# barometr.net
KiCad netlist of a schematic drawn in EAGLE
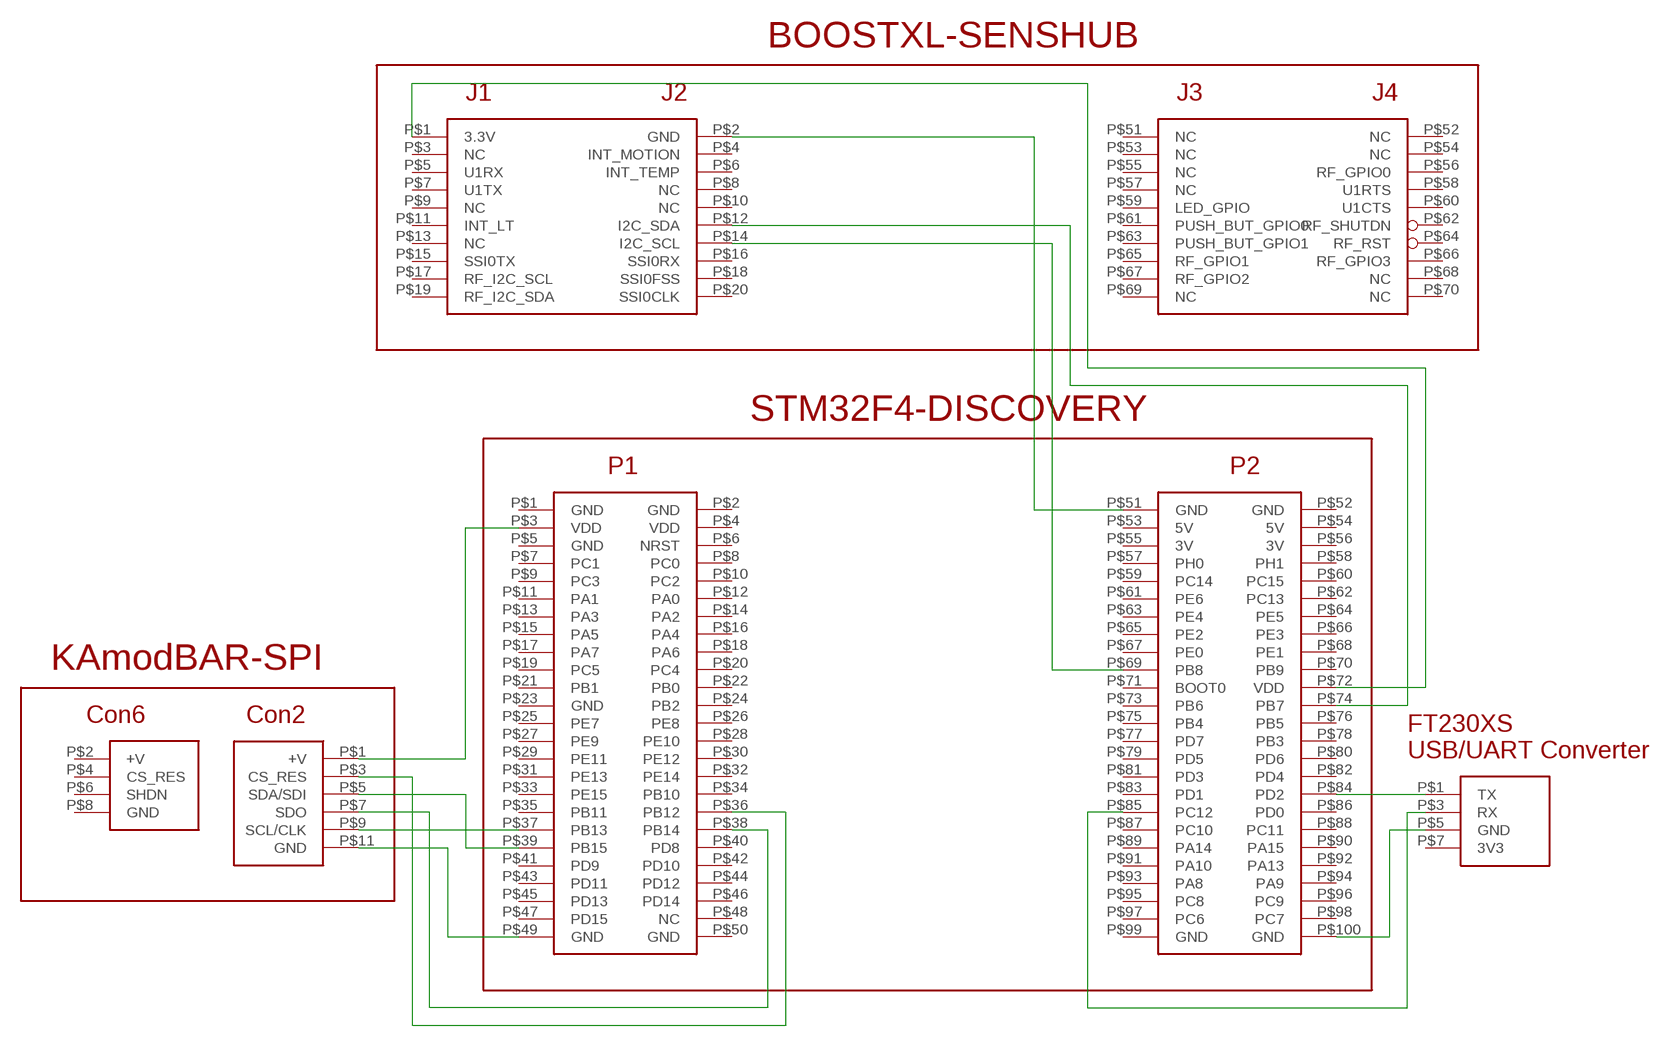
[diagram p0: schematic, sheet 1]

(export (version "E")
  (design (tool "Eeschema 10.0.6"))
  (components
    (comp (ref "U$1")
      (value "STM32F4-DISCOVERY")
      (footprint "eagle-import:STM32F4-DISCOVERY")
      (libsource (lib "eagle-import") (part "STM32F4-DISCOVERY"))
    )
    (comp (ref "U$2")
      (value "BOOSTXL-SENSHUB")
      (footprint "eagle-import:BOOSTXL-SENSHUB")
      (libsource (lib "eagle-import") (part "BOOSTXL-SENSHUB"))
    )
    (comp (ref "U$3")
      (value "KAMODBAR-SPI")
      (footprint "eagle-import:KAMODBAR-SPI")
      (libsource (lib "eagle-import") (part "KAMODBAR-SPI"))
    )
    (comp (ref "U$4")
      (value "FT230XS_UART_USB_CONVERTER")
      (footprint "eagle-import:FT230XS_UART_USB_CONVERTER")
      (libsource (lib "eagle-import") (part "FT230XS_UART_USB_CONVERTER"))
    )
  )
  (nets
    (net (code "1") (name "Net-(U$1-GND-PadP$49)") (class "Default")
      (node (ref "U$1") (pin "P$49") (pinfunction "GND_P$49") (pintype "bidirectional"))
      (node (ref "U$3") (pin "P$11") (pinfunction "GND_P$11") (pintype "bidirectional"))
    )
    (net (code "2") (name "Net-(U$1-PB7)") (class "Default")
      (node (ref "U$1") (pin "P$74") (pinfunction "PB7_P$74") (pintype "bidirectional"))
      (node (ref "U$2") (pin "P$12") (pinfunction "I2C_SDA_P$12") (pintype "bidirectional"))
    )
    (net (code "3") (name "Net-(U$1-PB8)") (class "Default")
      (node (ref "U$1") (pin "P$69") (pinfunction "PB8_P$69") (pintype "bidirectional"))
      (node (ref "U$2") (pin "P$14") (pinfunction "I2C_SCL_P$14") (pintype "bidirectional"))
    )
    (net (code "4") (name "Net-(U$1-PB12)") (class "Default")
      (node (ref "U$1") (pin "P$36") (pinfunction "PB12_P$36") (pintype "bidirectional"))
      (node (ref "U$3") (pin "P$3") (pinfunction "CS_RES_P$3") (pintype "bidirectional"))
    )
    (net (code "5") (name "Net-(U$1-PB13)") (class "Default")
      (node (ref "U$1") (pin "P$37") (pinfunction "PB13_P$37") (pintype "bidirectional"))
      (node (ref "U$3") (pin "P$9") (pinfunction "SCL/CLK_P$9") (pintype "bidirectional"))
    )
    (net (code "6") (name "Net-(U$1-PB14)") (class "Default")
      (node (ref "U$1") (pin "P$38") (pinfunction "PB14_P$38") (pintype "bidirectional"))
      (node (ref "U$3") (pin "P$7") (pinfunction "SDO_P$7") (pintype "bidirectional"))
    )
    (net (code "7") (name "Net-(U$1-PB15)") (class "Default")
      (node (ref "U$1") (pin "P$39") (pinfunction "PB15_P$39") (pintype "bidirectional"))
      (node (ref "U$3") (pin "P$5") (pinfunction "SDA/SDI_P$5") (pintype "bidirectional"))
    )
    (net (code "8") (name "Net-(U$1-PC12)") (class "Default")
      (node (ref "U$1") (pin "P$85") (pinfunction "PC12_P$85") (pintype "bidirectional"))
      (node (ref "U$4") (pin "P$3") (pinfunction "RX_P$3") (pintype "bidirectional"))
    )
    (net (code "9") (name "Net-(U$1-PD2)") (class "Default")
      (node (ref "U$1") (pin "P$84") (pinfunction "PD2_P$84") (pintype "bidirectional"))
      (node (ref "U$4") (pin "P$1") (pinfunction "TX_P$1") (pintype "bidirectional"))
    )
    (net (code "10") (name "Net-(U$1-VDD-PadP$3)") (class "Default")
      (node (ref "U$1") (pin "P$3") (pinfunction "VDD_P$3") (pintype "bidirectional"))
      (node (ref "U$3") (pin "P$1") (pinfunction "+V_P$1") (pintype "bidirectional"))
    )
    (net (code "11") (name "Net-(U$2-3.3V)") (class "Default")
      (node (ref "U$1") (pin "P$72") (pinfunction "VDD_P$72") (pintype "bidirectional"))
      (node (ref "U$2") (pin "P$1") (pinfunction "3.3V_P$1") (pintype "bidirectional"))
    )
    (net (code "12") (name "Net-(U$2-GND)") (class "Default")
      (node (ref "U$1") (pin "P$51") (pinfunction "GND_P$51") (pintype "bidirectional"))
      (node (ref "U$2") (pin "P$2") (pinfunction "GND_P$2") (pintype "bidirectional"))
    )
    (net (code "13") (name "Net-(U$4-GND)") (class "Default")
      (node (ref "U$1") (pin "P$100") (pinfunction "GND_P$100") (pintype "bidirectional"))
      (node (ref "U$4") (pin "P$5") (pinfunction "GND_P$5") (pintype "bidirectional"))
    )
    (net (code "14") (name "unconnected-(U$1-3V-PadP$55)") (class "Default")
      (node (ref "U$1") (pin "P$55") (pinfunction "3V_P$55") (pintype "bidirectional"))
    )
    (net (code "15") (name "unconnected-(U$1-3V-PadP$56)") (class "Default")
      (node (ref "U$1") (pin "P$56") (pinfunction "3V_P$56") (pintype "bidirectional"))
    )
    (net (code "16") (name "unconnected-(U$1-5V-PadP$53)") (class "Default")
      (node (ref "U$1") (pin "P$53") (pinfunction "5V_P$53") (pintype "bidirectional"))
    )
    (net (code "17") (name "unconnected-(U$1-5V-PadP$54)") (class "Default")
      (node (ref "U$1") (pin "P$54") (pinfunction "5V_P$54") (pintype "bidirectional"))
    )
    (net (code "18") (name "unconnected-(U$1-BOOT0-PadP$71)") (class "Default")
      (node (ref "U$1") (pin "P$71") (pinfunction "BOOT0_P$71") (pintype "bidirectional"))
    )
    (net (code "19") (name "unconnected-(U$1-GND-PadP$1)") (class "Default")
      (node (ref "U$1") (pin "P$1") (pinfunction "GND_P$1") (pintype "bidirectional"))
    )
    (net (code "20") (name "unconnected-(U$1-GND-PadP$2)") (class "Default")
      (node (ref "U$1") (pin "P$2") (pinfunction "GND_P$2") (pintype "bidirectional"))
    )
    (net (code "21") (name "unconnected-(U$1-GND-PadP$5)") (class "Default")
      (node (ref "U$1") (pin "P$5") (pinfunction "GND_P$5") (pintype "bidirectional"))
    )
    (net (code "22") (name "unconnected-(U$1-GND-PadP$23)") (class "Default")
      (node (ref "U$1") (pin "P$23") (pinfunction "GND_P$23") (pintype "bidirectional"))
    )
    (net (code "23") (name "unconnected-(U$1-GND-PadP$50)") (class "Default")
      (node (ref "U$1") (pin "P$50") (pinfunction "GND_P$50") (pintype "bidirectional"))
    )
    (net (code "24") (name "unconnected-(U$1-GND-PadP$52)") (class "Default")
      (node (ref "U$1") (pin "P$52") (pinfunction "GND_P$52") (pintype "bidirectional"))
    )
    (net (code "25") (name "unconnected-(U$1-GND-PadP$99)") (class "Default")
      (node (ref "U$1") (pin "P$99") (pinfunction "GND_P$99") (pintype "bidirectional"))
    )
    (net (code "26") (name "unconnected-(U$1-NC-PadP$48)") (class "Default")
      (node (ref "U$1") (pin "P$48") (pinfunction "NC_P$48") (pintype "bidirectional"))
    )
    (net (code "27") (name "unconnected-(U$1-NRST-PadP$6)") (class "Default")
      (node (ref "U$1") (pin "P$6") (pinfunction "NRST_P$6") (pintype "bidirectional"))
    )
    (net (code "28") (name "unconnected-(U$1-PA0-PadP$12)") (class "Default")
      (node (ref "U$1") (pin "P$12") (pinfunction "PA0_P$12") (pintype "bidirectional"))
    )
    (net (code "29") (name "unconnected-(U$1-PA1-PadP$11)") (class "Default")
      (node (ref "U$1") (pin "P$11") (pinfunction "PA1_P$11") (pintype "bidirectional"))
    )
    (net (code "30") (name "unconnected-(U$1-PA2-PadP$14)") (class "Default")
      (node (ref "U$1") (pin "P$14") (pinfunction "PA2_P$14") (pintype "bidirectional"))
    )
    (net (code "31") (name "unconnected-(U$1-PA3-PadP$13)") (class "Default")
      (node (ref "U$1") (pin "P$13") (pinfunction "PA3_P$13") (pintype "bidirectional"))
    )
    (net (code "32") (name "unconnected-(U$1-PA4-PadP$16)") (class "Default")
      (node (ref "U$1") (pin "P$16") (pinfunction "PA4_P$16") (pintype "bidirectional"))
    )
    (net (code "33") (name "unconnected-(U$1-PA5-PadP$15)") (class "Default")
      (node (ref "U$1") (pin "P$15") (pinfunction "PA5_P$15") (pintype "bidirectional"))
    )
    (net (code "34") (name "unconnected-(U$1-PA6-PadP$18)") (class "Default")
      (node (ref "U$1") (pin "P$18") (pinfunction "PA6_P$18") (pintype "bidirectional"))
    )
    (net (code "35") (name "unconnected-(U$1-PA7-PadP$17)") (class "Default")
      (node (ref "U$1") (pin "P$17") (pinfunction "PA7_P$17") (pintype "bidirectional"))
    )
    (net (code "36") (name "unconnected-(U$1-PA8-PadP$93)") (class "Default")
      (node (ref "U$1") (pin "P$93") (pinfunction "PA8_P$93") (pintype "bidirectional"))
    )
    (net (code "37") (name "unconnected-(U$1-PA9-PadP$94)") (class "Default")
      (node (ref "U$1") (pin "P$94") (pinfunction "PA9_P$94") (pintype "bidirectional"))
    )
    (net (code "38") (name "unconnected-(U$1-PA10-PadP$91)") (class "Default")
      (node (ref "U$1") (pin "P$91") (pinfunction "PA10_P$91") (pintype "bidirectional"))
    )
    (net (code "39") (name "unconnected-(U$1-PA13-PadP$92)") (class "Default")
      (node (ref "U$1") (pin "P$92") (pinfunction "PA13_P$92") (pintype "bidirectional"))
    )
    (net (code "40") (name "unconnected-(U$1-PA14-PadP$89)") (class "Default")
      (node (ref "U$1") (pin "P$89") (pinfunction "PA14_P$89") (pintype "bidirectional"))
    )
    (net (code "41") (name "unconnected-(U$1-PA15-PadP$90)") (class "Default")
      (node (ref "U$1") (pin "P$90") (pinfunction "PA15_P$90") (pintype "bidirectional"))
    )
    (net (code "42") (name "unconnected-(U$1-PB0-PadP$22)") (class "Default")
      (node (ref "U$1") (pin "P$22") (pinfunction "PB0_P$22") (pintype "bidirectional"))
    )
    (net (code "43") (name "unconnected-(U$1-PB1-PadP$21)") (class "Default")
      (node (ref "U$1") (pin "P$21") (pinfunction "PB1_P$21") (pintype "bidirectional"))
    )
    (net (code "44") (name "unconnected-(U$1-PB2-PadP$24)") (class "Default")
      (node (ref "U$1") (pin "P$24") (pinfunction "PB2_P$24") (pintype "bidirectional"))
    )
    (net (code "45") (name "unconnected-(U$1-PB3-PadP$78)") (class "Default")
      (node (ref "U$1") (pin "P$78") (pinfunction "PB3_P$78") (pintype "bidirectional"))
    )
    (net (code "46") (name "unconnected-(U$1-PB4-PadP$75)") (class "Default")
      (node (ref "U$1") (pin "P$75") (pinfunction "PB4_P$75") (pintype "bidirectional"))
    )
    (net (code "47") (name "unconnected-(U$1-PB5-PadP$76)") (class "Default")
      (node (ref "U$1") (pin "P$76") (pinfunction "PB5_P$76") (pintype "bidirectional"))
    )
    (net (code "48") (name "unconnected-(U$1-PB6-PadP$73)") (class "Default")
      (node (ref "U$1") (pin "P$73") (pinfunction "PB6_P$73") (pintype "bidirectional"))
    )
    (net (code "49") (name "unconnected-(U$1-PB9-PadP$70)") (class "Default")
      (node (ref "U$1") (pin "P$70") (pinfunction "PB9_P$70") (pintype "bidirectional"))
    )
    (net (code "50") (name "unconnected-(U$1-PB10-PadP$34)") (class "Default")
      (node (ref "U$1") (pin "P$34") (pinfunction "PB10_P$34") (pintype "bidirectional"))
    )
    (net (code "51") (name "unconnected-(U$1-PB11-PadP$35)") (class "Default")
      (node (ref "U$1") (pin "P$35") (pinfunction "PB11_P$35") (pintype "bidirectional"))
    )
    (net (code "52") (name "unconnected-(U$1-PC0-PadP$8)") (class "Default")
      (node (ref "U$1") (pin "P$8") (pinfunction "PC0_P$8") (pintype "bidirectional"))
    )
    (net (code "53") (name "unconnected-(U$1-PC1-PadP$7)") (class "Default")
      (node (ref "U$1") (pin "P$7") (pinfunction "PC1_P$7") (pintype "bidirectional"))
    )
    (net (code "54") (name "unconnected-(U$1-PC2-PadP$10)") (class "Default")
      (node (ref "U$1") (pin "P$10") (pinfunction "PC2_P$10") (pintype "bidirectional"))
    )
    (net (code "55") (name "unconnected-(U$1-PC3-PadP$9)") (class "Default")
      (node (ref "U$1") (pin "P$9") (pinfunction "PC3_P$9") (pintype "bidirectional"))
    )
    (net (code "56") (name "unconnected-(U$1-PC4-PadP$20)") (class "Default")
      (node (ref "U$1") (pin "P$20") (pinfunction "PC4_P$20") (pintype "bidirectional"))
    )
    (net (code "57") (name "unconnected-(U$1-PC5-PadP$19)") (class "Default")
      (node (ref "U$1") (pin "P$19") (pinfunction "PC5_P$19") (pintype "bidirectional"))
    )
    (net (code "58") (name "unconnected-(U$1-PC6-PadP$97)") (class "Default")
      (node (ref "U$1") (pin "P$97") (pinfunction "PC6_P$97") (pintype "bidirectional"))
    )
    (net (code "59") (name "unconnected-(U$1-PC7-PadP$98)") (class "Default")
      (node (ref "U$1") (pin "P$98") (pinfunction "PC7_P$98") (pintype "bidirectional"))
    )
    (net (code "60") (name "unconnected-(U$1-PC8-PadP$95)") (class "Default")
      (node (ref "U$1") (pin "P$95") (pinfunction "PC8_P$95") (pintype "bidirectional"))
    )
    (net (code "61") (name "unconnected-(U$1-PC9-PadP$96)") (class "Default")
      (node (ref "U$1") (pin "P$96") (pinfunction "PC9_P$96") (pintype "bidirectional"))
    )
    (net (code "62") (name "unconnected-(U$1-PC10-PadP$87)") (class "Default")
      (node (ref "U$1") (pin "P$87") (pinfunction "PC10_P$87") (pintype "bidirectional"))
    )
    (net (code "63") (name "unconnected-(U$1-PC11-PadP$88)") (class "Default")
      (node (ref "U$1") (pin "P$88") (pinfunction "PC11_P$88") (pintype "bidirectional"))
    )
    (net (code "64") (name "unconnected-(U$1-PC13-PadP$62)") (class "Default")
      (node (ref "U$1") (pin "P$62") (pinfunction "PC13_P$62") (pintype "bidirectional"))
    )
    (net (code "65") (name "unconnected-(U$1-PC14-PadP$59)") (class "Default")
      (node (ref "U$1") (pin "P$59") (pinfunction "PC14_P$59") (pintype "bidirectional"))
    )
    (net (code "66") (name "unconnected-(U$1-PC15-PadP$60)") (class "Default")
      (node (ref "U$1") (pin "P$60") (pinfunction "PC15_P$60") (pintype "bidirectional"))
    )
    (net (code "67") (name "unconnected-(U$1-PD0-PadP$86)") (class "Default")
      (node (ref "U$1") (pin "P$86") (pinfunction "PD0_P$86") (pintype "bidirectional"))
    )
    (net (code "68") (name "unconnected-(U$1-PD1-PadP$83)") (class "Default")
      (node (ref "U$1") (pin "P$83") (pinfunction "PD1_P$83") (pintype "bidirectional"))
    )
    (net (code "69") (name "unconnected-(U$1-PD3-PadP$81)") (class "Default")
      (node (ref "U$1") (pin "P$81") (pinfunction "PD3_P$81") (pintype "bidirectional"))
    )
    (net (code "70") (name "unconnected-(U$1-PD4-PadP$82)") (class "Default")
      (node (ref "U$1") (pin "P$82") (pinfunction "PD4_P$82") (pintype "bidirectional"))
    )
    (net (code "71") (name "unconnected-(U$1-PD5-PadP$79)") (class "Default")
      (node (ref "U$1") (pin "P$79") (pinfunction "PD5_P$79") (pintype "bidirectional"))
    )
    (net (code "72") (name "unconnected-(U$1-PD6-PadP$80)") (class "Default")
      (node (ref "U$1") (pin "P$80") (pinfunction "PD6_P$80") (pintype "bidirectional"))
    )
    (net (code "73") (name "unconnected-(U$1-PD7-PadP$77)") (class "Default")
      (node (ref "U$1") (pin "P$77") (pinfunction "PD7_P$77") (pintype "bidirectional"))
    )
    (net (code "74") (name "unconnected-(U$1-PD8-PadP$40)") (class "Default")
      (node (ref "U$1") (pin "P$40") (pinfunction "PD8_P$40") (pintype "bidirectional"))
    )
    (net (code "75") (name "unconnected-(U$1-PD9-PadP$41)") (class "Default")
      (node (ref "U$1") (pin "P$41") (pinfunction "PD9_P$41") (pintype "bidirectional"))
    )
    (net (code "76") (name "unconnected-(U$1-PD10-PadP$42)") (class "Default")
      (node (ref "U$1") (pin "P$42") (pinfunction "PD10_P$42") (pintype "bidirectional"))
    )
    (net (code "77") (name "unconnected-(U$1-PD11-PadP$43)") (class "Default")
      (node (ref "U$1") (pin "P$43") (pinfunction "PD11_P$43") (pintype "bidirectional"))
    )
    (net (code "78") (name "unconnected-(U$1-PD12-PadP$44)") (class "Default")
      (node (ref "U$1") (pin "P$44") (pinfunction "PD12_P$44") (pintype "bidirectional"))
    )
    (net (code "79") (name "unconnected-(U$1-PD13-PadP$45)") (class "Default")
      (node (ref "U$1") (pin "P$45") (pinfunction "PD13_P$45") (pintype "bidirectional"))
    )
    (net (code "80") (name "unconnected-(U$1-PD14-PadP$46)") (class "Default")
      (node (ref "U$1") (pin "P$46") (pinfunction "PD14_P$46") (pintype "bidirectional"))
    )
    (net (code "81") (name "unconnected-(U$1-PD15-PadP$47)") (class "Default")
      (node (ref "U$1") (pin "P$47") (pinfunction "PD15_P$47") (pintype "bidirectional"))
    )
    (net (code "82") (name "unconnected-(U$1-PE0-PadP$67)") (class "Default")
      (node (ref "U$1") (pin "P$67") (pinfunction "PE0_P$67") (pintype "bidirectional"))
    )
    (net (code "83") (name "unconnected-(U$1-PE1-PadP$68)") (class "Default")
      (node (ref "U$1") (pin "P$68") (pinfunction "PE1_P$68") (pintype "bidirectional"))
    )
    (net (code "84") (name "unconnected-(U$1-PE2-PadP$65)") (class "Default")
      (node (ref "U$1") (pin "P$65") (pinfunction "PE2_P$65") (pintype "bidirectional"))
    )
    (net (code "85") (name "unconnected-(U$1-PE3-PadP$66)") (class "Default")
      (node (ref "U$1") (pin "P$66") (pinfunction "PE3_P$66") (pintype "bidirectional"))
    )
    (net (code "86") (name "unconnected-(U$1-PE4-PadP$63)") (class "Default")
      (node (ref "U$1") (pin "P$63") (pinfunction "PE4_P$63") (pintype "bidirectional"))
    )
    (net (code "87") (name "unconnected-(U$1-PE5-PadP$64)") (class "Default")
      (node (ref "U$1") (pin "P$64") (pinfunction "PE5_P$64") (pintype "bidirectional"))
    )
    (net (code "88") (name "unconnected-(U$1-PE6-PadP$61)") (class "Default")
      (node (ref "U$1") (pin "P$61") (pinfunction "PE6_P$61") (pintype "bidirectional"))
    )
    (net (code "89") (name "unconnected-(U$1-PE7-PadP$25)") (class "Default")
      (node (ref "U$1") (pin "P$25") (pinfunction "PE7_P$25") (pintype "bidirectional"))
    )
    (net (code "90") (name "unconnected-(U$1-PE8-PadP$26)") (class "Default")
      (node (ref "U$1") (pin "P$26") (pinfunction "PE8_P$26") (pintype "bidirectional"))
    )
    (net (code "91") (name "unconnected-(U$1-PE9-PadP$27)") (class "Default")
      (node (ref "U$1") (pin "P$27") (pinfunction "PE9_P$27") (pintype "bidirectional"))
    )
    (net (code "92") (name "unconnected-(U$1-PE10-PadP$28)") (class "Default")
      (node (ref "U$1") (pin "P$28") (pinfunction "PE10_P$28") (pintype "bidirectional"))
    )
    (net (code "93") (name "unconnected-(U$1-PE11-PadP$29)") (class "Default")
      (node (ref "U$1") (pin "P$29") (pinfunction "PE11_P$29") (pintype "bidirectional"))
    )
    (net (code "94") (name "unconnected-(U$1-PE12-PadP$30)") (class "Default")
      (node (ref "U$1") (pin "P$30") (pinfunction "PE12_P$30") (pintype "bidirectional"))
    )
    (net (code "95") (name "unconnected-(U$1-PE13-PadP$31)") (class "Default")
      (node (ref "U$1") (pin "P$31") (pinfunction "PE13_P$31") (pintype "bidirectional"))
    )
    (net (code "96") (name "unconnected-(U$1-PE14-PadP$32)") (class "Default")
      (node (ref "U$1") (pin "P$32") (pinfunction "PE14_P$32") (pintype "bidirectional"))
    )
    (net (code "97") (name "unconnected-(U$1-PE15-PadP$33)") (class "Default")
      (node (ref "U$1") (pin "P$33") (pinfunction "PE15_P$33") (pintype "bidirectional"))
    )
    (net (code "98") (name "unconnected-(U$1-PH0-PadP$57)") (class "Default")
      (node (ref "U$1") (pin "P$57") (pinfunction "PH0_P$57") (pintype "bidirectional"))
    )
    (net (code "99") (name "unconnected-(U$1-PH1-PadP$58)") (class "Default")
      (node (ref "U$1") (pin "P$58") (pinfunction "PH1_P$58") (pintype "bidirectional"))
    )
    (net (code "100") (name "unconnected-(U$1-VDD-PadP$4)") (class "Default")
      (node (ref "U$1") (pin "P$4") (pinfunction "VDD_P$4") (pintype "bidirectional"))
    )
    (net (code "101") (name "unconnected-(U$2-INT_LT-PadP$11)") (class "Default")
      (node (ref "U$2") (pin "P$11") (pinfunction "INT_LT_P$11") (pintype "bidirectional"))
    )
    (net (code "102") (name "unconnected-(U$2-INT_MOTION-PadP$4)") (class "Default")
      (node (ref "U$2") (pin "P$4") (pinfunction "INT_MOTION_P$4") (pintype "bidirectional"))
    )
    (net (code "103") (name "unconnected-(U$2-INT_TEMP-PadP$6)") (class "Default")
      (node (ref "U$2") (pin "P$6") (pinfunction "INT_TEMP_P$6") (pintype "bidirectional"))
    )
    (net (code "104") (name "unconnected-(U$2-LED_GPIO-PadP$59)") (class "Default")
      (node (ref "U$2") (pin "P$59") (pinfunction "LED_GPIO_P$59") (pintype "bidirectional"))
    )
    (net (code "105") (name "unconnected-(U$2-NC-PadP$3)") (class "Default")
      (node (ref "U$2") (pin "P$3") (pinfunction "NC_P$3") (pintype "bidirectional"))
    )
    (net (code "106") (name "unconnected-(U$2-NC-PadP$8)") (class "Default")
      (node (ref "U$2") (pin "P$8") (pinfunction "NC_P$8") (pintype "bidirectional"))
    )
    (net (code "107") (name "unconnected-(U$2-NC-PadP$9)") (class "Default")
      (node (ref "U$2") (pin "P$9") (pinfunction "NC_P$9") (pintype "bidirectional"))
    )
    (net (code "108") (name "unconnected-(U$2-NC-PadP$10)") (class "Default")
      (node (ref "U$2") (pin "P$10") (pinfunction "NC_P$10") (pintype "bidirectional"))
    )
    (net (code "109") (name "unconnected-(U$2-NC-PadP$13)") (class "Default")
      (node (ref "U$2") (pin "P$13") (pinfunction "NC_P$13") (pintype "bidirectional"))
    )
    (net (code "110") (name "unconnected-(U$2-NC-PadP$51)") (class "Default")
      (node (ref "U$2") (pin "P$51") (pinfunction "NC_P$51") (pintype "bidirectional"))
    )
    (net (code "111") (name "unconnected-(U$2-NC-PadP$52)") (class "Default")
      (node (ref "U$2") (pin "P$52") (pinfunction "NC_P$52") (pintype "bidirectional"))
    )
    (net (code "112") (name "unconnected-(U$2-NC-PadP$53)") (class "Default")
      (node (ref "U$2") (pin "P$53") (pinfunction "NC_P$53") (pintype "bidirectional"))
    )
    (net (code "113") (name "unconnected-(U$2-NC-PadP$54)") (class "Default")
      (node (ref "U$2") (pin "P$54") (pinfunction "NC_P$54") (pintype "bidirectional"))
    )
    (net (code "114") (name "unconnected-(U$2-NC-PadP$55)") (class "Default")
      (node (ref "U$2") (pin "P$55") (pinfunction "NC_P$55") (pintype "bidirectional"))
    )
    (net (code "115") (name "unconnected-(U$2-NC-PadP$57)") (class "Default")
      (node (ref "U$2") (pin "P$57") (pinfunction "NC_P$57") (pintype "bidirectional"))
    )
    (net (code "116") (name "unconnected-(U$2-NC-PadP$68)") (class "Default")
      (node (ref "U$2") (pin "P$68") (pinfunction "NC_P$68") (pintype "bidirectional"))
    )
    (net (code "117") (name "unconnected-(U$2-NC-PadP$69)") (class "Default")
      (node (ref "U$2") (pin "P$69") (pinfunction "NC_P$69") (pintype "bidirectional"))
    )
    (net (code "118") (name "unconnected-(U$2-NC-PadP$70)") (class "Default")
      (node (ref "U$2") (pin "P$70") (pinfunction "NC_P$70") (pintype "bidirectional"))
    )
    (net (code "119") (name "unconnected-(U$2-PUSH_BUT_GPIO0-PadP$61)") (class "Default")
      (node (ref "U$2") (pin "P$61") (pinfunction "PUSH_BUT_GPIO0_P$61") (pintype "bidirectional"))
    )
    (net (code "120") (name "unconnected-(U$2-PUSH_BUT_GPIO1-PadP$63)") (class "Default")
      (node (ref "U$2") (pin "P$63") (pinfunction "PUSH_BUT_GPIO1_P$63") (pintype "bidirectional"))
    )
    (net (code "121") (name "unconnected-(U$2-RF_GPIO0-PadP$56)") (class "Default")
      (node (ref "U$2") (pin "P$56") (pinfunction "RF_GPIO0_P$56") (pintype "bidirectional"))
    )
    (net (code "122") (name "unconnected-(U$2-RF_GPIO1-PadP$65)") (class "Default")
      (node (ref "U$2") (pin "P$65") (pinfunction "RF_GPIO1_P$65") (pintype "bidirectional"))
    )
    (net (code "123") (name "unconnected-(U$2-RF_GPIO2-PadP$67)") (class "Default")
      (node (ref "U$2") (pin "P$67") (pinfunction "RF_GPIO2_P$67") (pintype "bidirectional"))
    )
    (net (code "124") (name "unconnected-(U$2-RF_GPIO3-PadP$66)") (class "Default")
      (node (ref "U$2") (pin "P$66") (pinfunction "RF_GPIO3_P$66") (pintype "bidirectional"))
    )
    (net (code "125") (name "unconnected-(U$2-RF_I2C_SCL-PadP$17)") (class "Default")
      (node (ref "U$2") (pin "P$17") (pinfunction "RF_I2C_SCL_P$17") (pintype "bidirectional"))
    )
    (net (code "126") (name "unconnected-(U$2-RF_I2C_SDA-PadP$19)") (class "Default")
      (node (ref "U$2") (pin "P$19") (pinfunction "RF_I2C_SDA_P$19") (pintype "bidirectional"))
    )
    (net (code "127") (name "unconnected-(U$2-RF_RST-PadP$64)") (class "Default")
      (node (ref "U$2") (pin "P$64") (pinfunction "RF_RST_P$64") (pintype "bidirectional"))
    )
    (net (code "128") (name "unconnected-(U$2-RF_SHUTDN-PadP$62)") (class "Default")
      (node (ref "U$2") (pin "P$62") (pinfunction "RF_SHUTDN_P$62") (pintype "bidirectional"))
    )
    (net (code "129") (name "unconnected-(U$2-SSI0CLK-PadP$20)") (class "Default")
      (node (ref "U$2") (pin "P$20") (pinfunction "SSI0CLK_P$20") (pintype "bidirectional"))
    )
    (net (code "130") (name "unconnected-(U$2-SSI0FSS-PadP$18)") (class "Default")
      (node (ref "U$2") (pin "P$18") (pinfunction "SSI0FSS_P$18") (pintype "bidirectional"))
    )
    (net (code "131") (name "unconnected-(U$2-SSI0RX-PadP$16)") (class "Default")
      (node (ref "U$2") (pin "P$16") (pinfunction "SSI0RX_P$16") (pintype "bidirectional"))
    )
    (net (code "132") (name "unconnected-(U$2-SSI0TX-PadP$15)") (class "Default")
      (node (ref "U$2") (pin "P$15") (pinfunction "SSI0TX_P$15") (pintype "bidirectional"))
    )
    (net (code "133") (name "unconnected-(U$2-U1CTS-PadP$60)") (class "Default")
      (node (ref "U$2") (pin "P$60") (pinfunction "U1CTS_P$60") (pintype "bidirectional"))
    )
    (net (code "134") (name "unconnected-(U$2-U1RTS-PadP$58)") (class "Default")
      (node (ref "U$2") (pin "P$58") (pinfunction "U1RTS_P$58") (pintype "bidirectional"))
    )
    (net (code "135") (name "unconnected-(U$2-U1RX-PadP$5)") (class "Default")
      (node (ref "U$2") (pin "P$5") (pinfunction "U1RX_P$5") (pintype "bidirectional"))
    )
    (net (code "136") (name "unconnected-(U$2-U1TX-PadP$7)") (class "Default")
      (node (ref "U$2") (pin "P$7") (pinfunction "U1TX_P$7") (pintype "bidirectional"))
    )
    (net (code "137") (name "unconnected-(U$3-+V-PadP$2)") (class "Default")
      (node (ref "U$3") (pin "P$2") (pinfunction "+V_P$2") (pintype "bidirectional"))
    )
    (net (code "138") (name "unconnected-(U$3-CS_RES-PadP$4)") (class "Default")
      (node (ref "U$3") (pin "P$4") (pinfunction "CS_RES_P$4") (pintype "bidirectional"))
    )
    (net (code "139") (name "unconnected-(U$3-GND-PadP$8)") (class "Default")
      (node (ref "U$3") (pin "P$8") (pinfunction "GND_P$8") (pintype "bidirectional"))
    )
    (net (code "140") (name "unconnected-(U$3-SHDN-PadP$6)") (class "Default")
      (node (ref "U$3") (pin "P$6") (pinfunction "SHDN_P$6") (pintype "bidirectional"))
    )
    (net (code "141") (name "unconnected-(U$4-3V3-PadP$7)") (class "Default")
      (node (ref "U$4") (pin "P$7") (pinfunction "3V3_P$7") (pintype "bidirectional"))
    )
  )
)
